# dym.net
KiCad netlist of a schematic drawn in Altium Designer
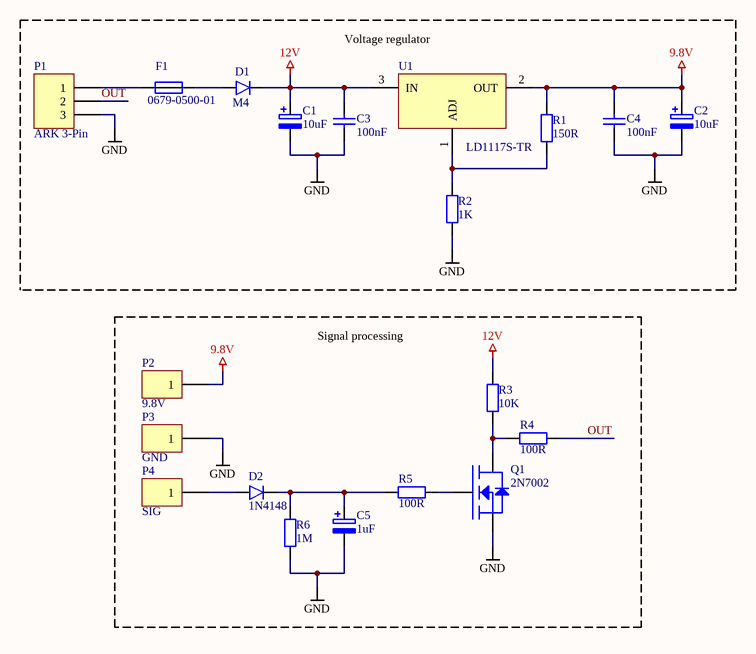
[diagram p0: dym.SchDoc]

(export (version "E")
  (design (tool "Eeschema 10.0.6"))
  (components
    (comp (ref "C1")
      (value "10uF")
      (footprint "TANC_B")
      (description "Capacitor Polarized")
      (libsource (lib "Library") (part "Cap_Pol"))
    )
    (comp (ref "C2")
      (value "10uF")
      (footprint "TANC_B")
      (description "Capacitor Polarized")
      (libsource (lib "Library") (part "Cap_Pol"))
    )
    (comp (ref "C3")
      (value "100nF")
      (footprint "C0805")
      (description "Capacitor")
      (libsource (lib "Library") (part "Cap"))
    )
    (comp (ref "C4")
      (value "100nF")
      (footprint "C0805")
      (description "Capacitor")
      (libsource (lib "Library") (part "Cap"))
    )
    (comp (ref "C5")
      (value "1uF")
      (footprint "TANC_A")
      (description "Capacitor Polarized")
      (libsource (lib "Library") (part "Cap_Pol"))
    )
    (comp (ref "D1") (value "M4") (footprint "SMA") (libsource (lib "Library") (part "Diode")))
    (comp (ref "D2") (value "1N4148") (footprint "DO-213A") (libsource (lib "Library") (part "Diode")))
    (comp (ref "F1")
      (value "0679-0500-01")
      (footprint "0679-0500-01")
      (description "Bezpiecznik: topikowy; szybki; ceramiczny; 500mA; 125VAC; 125VDC")
      (libsource (lib "Library") (part "0679-0500-01"))
    )
    (comp (ref "P1")
      (value "ARK 3-Pin")
      (footprint "ARK-3.5mm-3pin")
      (libsource (lib "Connectors") (part "ARK 3-Pin"))
    )
    (comp (ref "P2")
      (value "9.8V")
      (footprint "PAD")
      (description "PAD")
      (libsource (lib "Connectors") (part "PAD"))
    )
    (comp (ref "P3")
      (value "GND")
      (footprint "PAD")
      (description "PAD")
      (libsource (lib "Connectors") (part "PAD"))
    )
    (comp (ref "P4")
      (value "SIG")
      (footprint "PAD")
      (description "PAD")
      (libsource (lib "Connectors") (part "PAD"))
    )
    (comp (ref "Q1")
      (value "2N7002")
      (footprint "SOT23")
      (description "N-MOSFET")
      (libsource (lib "Library") (part "2N7002(GSD)"))
    )
    (comp (ref "R1")
      (value "150R")
      (footprint "R0805")
      (description "Resistor")
      (libsource (lib "") (part "Res_1"))
    )
    (comp (ref "R2")
      (value "1K")
      (footprint "R0805")
      (description "Resistor")
      (libsource (lib "") (part "Res_1"))
    )
    (comp (ref "R3")
      (value "10K")
      (footprint "R0805")
      (description "Resistor")
      (libsource (lib "") (part "Res_1"))
    )
    (comp (ref "R4")
      (value "100R")
      (footprint "R0805")
      (description "Resistor")
      (libsource (lib "") (part "Res_2"))
    )
    (comp (ref "R5")
      (value "100R")
      (footprint "R0805")
      (description "Resistor")
      (libsource (lib "") (part "Res_2"))
    )
    (comp (ref "R6")
      (value "1M")
      (footprint "R0805")
      (description "Resistor")
      (libsource (lib "Library") (part "Res"))
    )
    (comp (ref "U1")
      (value "LD1117S-TR")
      (footprint "SOT-223")
      (description "Stabilizator napiêcia; LDO, liniowy, regulowany; 1,25÷15V; 0,95A")
      (libsource (lib "IC") (part "LD1117S-TR"))
    )
  )
  (nets
    (net (code "1") (name "/OUT") (class "Default")
      (node (ref "P1") (pin "2") (pinfunction "2_2") (pintype "passive"))
      (node (ref "R4") (pin "1") (pinfunction "1_1") (pintype "passive"))
    )
    (net (code "2") (name "9.8V") (class "Default")
      (node (ref "C2") (pin "1") (pinfunction "1_1") (pintype "passive"))
      (node (ref "C4") (pin "1") (pinfunction "1_1") (pintype "passive"))
      (node (ref "P2") (pin "1") (pinfunction "1_1") (pintype "passive"))
      (node (ref "R1") (pin "1") (pinfunction "1_1") (pintype "passive"))
      (node (ref "U1") (pin "2") (pinfunction "OUT_2") (pintype "power_in"))
    )
    (net (code "3") (name "12V") (class "Default")
      (node (ref "C1") (pin "1") (pinfunction "1_1") (pintype "passive"))
      (node (ref "C3") (pin "1") (pinfunction "1_1") (pintype "passive"))
      (node (ref "D1") (pin "1") (pinfunction "1_1") (pintype "power_in"))
      (node (ref "R3") (pin "1") (pinfunction "1_1") (pintype "passive"))
      (node (ref "U1") (pin "3") (pinfunction "IN_3") (pintype "power_in"))
    )
    (net (code "4") (name "GND") (class "Default")
      (node (ref "C1") (pin "2") (pinfunction "2_2") (pintype "passive"))
      (node (ref "C2") (pin "2") (pinfunction "2_2") (pintype "passive"))
      (node (ref "C3") (pin "2") (pinfunction "2_2") (pintype "passive"))
      (node (ref "C4") (pin "2") (pinfunction "2_2") (pintype "passive"))
      (node (ref "C5") (pin "2") (pinfunction "2_2") (pintype "passive"))
      (node (ref "P1") (pin "3") (pinfunction "3_3") (pintype "passive"))
      (node (ref "P3") (pin "1") (pinfunction "1_1") (pintype "passive"))
      (node (ref "Q1") (pin "2") (pinfunction "S_2") (pintype "passive"))
      (node (ref "R2") (pin "2") (pinfunction "2_2") (pintype "passive"))
      (node (ref "R6") (pin "1") (pinfunction "1_1") (pintype "passive"))
    )
    (net (code "5") (name "Net-(C5-Pad1)") (class "Default")
      (node (ref "C5") (pin "1") (pinfunction "1_1") (pintype "passive"))
      (node (ref "D2") (pin "1") (pinfunction "1_1") (pintype "power_in"))
      (node (ref "R5") (pin "2") (pinfunction "2_2") (pintype "passive"))
      (node (ref "R6") (pin "2") (pinfunction "2_2") (pintype "passive"))
    )
    (net (code "6") (name "Net-(D1-Pad2)") (class "Default")
      (node (ref "D1") (pin "2") (pinfunction "2_2") (pintype "power_in"))
      (node (ref "F1") (pin "2") (pinfunction "2_2") (pintype "passive"))
    )
    (net (code "7") (name "Net-(D2-Pad2)") (class "Default")
      (node (ref "D2") (pin "2") (pinfunction "2_2") (pintype "power_in"))
      (node (ref "P4") (pin "1") (pinfunction "1_1") (pintype "passive"))
    )
    (net (code "8") (name "Net-(F1-Pad1)") (class "Default")
      (node (ref "F1") (pin "1") (pinfunction "1_1") (pintype "passive"))
      (node (ref "P1") (pin "1") (pinfunction "1_1") (pintype "passive"))
    )
    (net (code "9") (name "Net-(Q1-D)") (class "Default")
      (node (ref "Q1") (pin "3") (pinfunction "D_3") (pintype "passive"))
      (node (ref "R3") (pin "2") (pinfunction "2_2") (pintype "passive"))
      (node (ref "R4") (pin "2") (pinfunction "2_2") (pintype "passive"))
    )
    (net (code "10") (name "Net-(Q1-G)") (class "Default")
      (node (ref "Q1") (pin "1") (pinfunction "G_1") (pintype "passive"))
      (node (ref "R5") (pin "1") (pinfunction "1_1") (pintype "passive"))
    )
    (net (code "11") (name "Net-(U1-ADJ)") (class "Default")
      (node (ref "R1") (pin "2") (pinfunction "2_2") (pintype "passive"))
      (node (ref "R2") (pin "1") (pinfunction "1_1") (pintype "passive"))
      (node (ref "U1") (pin "1") (pinfunction "ADJ_1") (pintype "power_in"))
    )
  )
)
